# 02-Power.net
KiCad netlist of a schematic drawn in Altium Designer
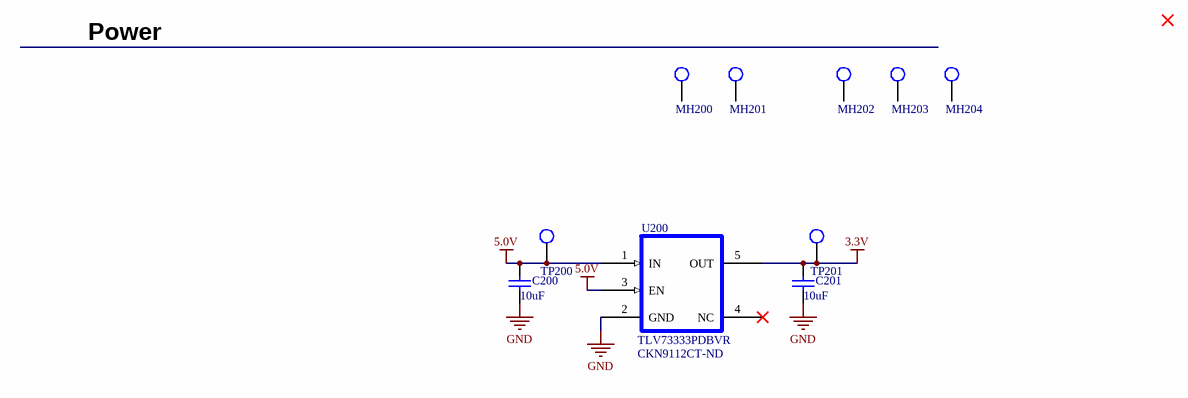
[diagram p0: 02-Power.SchDoc]

(export (version "E")
  (design (tool "Eeschema 10.0.6"))
  (components
    (comp (ref "C200")
      (value "10uF")
      (footprint "CAP_0805")
      (description "CAP CER 10UF 16V X5R 0805")
      (fields
        (field (name "MANUFACTURER") "Samsung")
        (field (name "MANUFACTURER PART NUMBER") "CL21A106KOFNNNE")
      )
      (libsource (lib "ece315") (part "CAP_0805_U_010.00"))
    )
    (comp (ref "C201")
      (value "10uF")
      (footprint "CAP_0805")
      (description "CAP CER 10UF 16V X5R 0805")
      (fields
        (field (name "MANUFACTURER") "Samsung")
        (field (name "MANUFACTURER PART NUMBER") "CL21A106KOFNNNE")
      )
      (libsource (lib "ece315") (part "CAP_0805_U_010.00"))
    )
    (comp (ref "MH200")
      (value "MHOLE_2_55MM")
      (footprint "MHOLE_2_55MM")
      (description "Mounting Holde")
      (fields (field (name "MANUFACTURER PART NUMBER") "UW MTHOLE"))
      (libsource (lib "ece315-2018-fall") (part "MHOLE_2_55MM"))
    )
    (comp (ref "MH201")
      (value "MHOLE_2_55MM")
      (footprint "MHOLE_2_55MM")
      (description "Mounting Holde")
      (fields (field (name "MANUFACTURER PART NUMBER") "UW MTHOLE"))
      (libsource (lib "ece315-2018-fall") (part "MHOLE_2_55MM"))
    )
    (comp (ref "MH202")
      (value "MHOLE_2_55MM")
      (footprint "MHOLE_2_55MM")
      (description "Mounting Holde")
      (fields (field (name "MANUFACTURER PART NUMBER") "UW MTHOLE"))
      (libsource (lib "ece315-2018-fall") (part "MHOLE_2_55MM"))
    )
    (comp (ref "MH203")
      (value "MHOLE_2_55MM")
      (footprint "MHOLE_2_55MM")
      (description "Mounting Holde")
      (fields (field (name "MANUFACTURER PART NUMBER") "UW MTHOLE"))
      (libsource (lib "ece315-2018-fall") (part "MHOLE_2_55MM"))
    )
    (comp (ref "MH204")
      (value "MHOLE_2_55MM")
      (footprint "MHOLE_2_55MM")
      (description "Mounting Holde")
      (fields (field (name "MANUFACTURER PART NUMBER") "UW MTHOLE"))
      (libsource (lib "ece315-2018-fall") (part "MHOLE_2_55MM"))
    )
    (comp (ref "TP200")
      (value "TP_1206")
      (footprint "TP-SMC-1206")
      (description "Test Point SMD 1206")
      (fields
        (field (name "MANUFACTURER") "TE Connectivity (Tyco Electronics)")
        (field (name "MANUFACTURER PART NUMBER") "1625854-1")
      )
      (libsource (lib "ece315") (part "TP_1206"))
    )
    (comp (ref "TP201")
      (value "TP_1206")
      (footprint "TP-SMC-1206")
      (description "Test Point SMD 1206")
      (fields
        (field (name "MANUFACTURER") "TE Connectivity (Tyco Electronics)")
        (field (name "MANUFACTURER PART NUMBER") "1625854-1")
      )
      (libsource (lib "ece315") (part "TP_1206"))
    )
    (comp (ref "U200")
      (value "TLV73333PDBVR")
      (footprint "IC_TLV73333PDBVR")
      (fields
        (field (name "MANUFACTURER") "Texas Instruments")
        (field (name "SUPPLIER PART NUMBER 1") "CKN9112CT-ND")
      )
      (libsource (lib "ece315") (part "TLV73333PDBVR"))
    )
  )
  (nets
    (net (code "1") (name "3.3V") (class "Default")
      (node (ref "C201") (pin "1") (pinfunction "1_1") (pintype "passive"))
      (node (ref "TP201") (pin "1") (pintype "passive"))
      (node (ref "U200") (pin "5") (pinfunction "OUT_5") (pintype "passive"))
    )
    (net (code "2") (name "5.0V") (class "Default")
      (node (ref "C200") (pin "1") (pinfunction "1_1") (pintype "passive"))
      (node (ref "TP200") (pin "1") (pintype "passive"))
      (node (ref "U200") (pin "1") (pinfunction "IN_1") (pintype "input"))
      (node (ref "U200") (pin "3") (pinfunction "EN_3") (pintype "input"))
    )
    (net (code "3") (name "GND") (class "Default")
      (node (ref "C200") (pin "2") (pinfunction "2_2") (pintype "passive"))
      (node (ref "C201") (pin "2") (pinfunction "2_2") (pintype "passive"))
      (node (ref "U200") (pin "2") (pinfunction "GND_2") (pintype "power_in"))
    )
    (net (code "4") (name "unconnected-(MH200-Pad1)") (class "Default")
      (node (ref "MH200") (pin "1") (pintype "passive"))
    )
    (net (code "5") (name "unconnected-(MH201-Pad1)") (class "Default")
      (node (ref "MH201") (pin "1") (pintype "passive"))
    )
    (net (code "6") (name "unconnected-(MH202-Pad1)") (class "Default")
      (node (ref "MH202") (pin "1") (pintype "passive"))
    )
    (net (code "7") (name "unconnected-(MH203-Pad1)") (class "Default")
      (node (ref "MH203") (pin "1") (pintype "passive"))
    )
    (net (code "8") (name "unconnected-(MH204-Pad1)") (class "Default")
      (node (ref "MH204") (pin "1") (pintype "passive"))
    )
    (net (code "9") (name "unconnected-(U200-NC-Pad4)") (class "Default")
      (node (ref "U200") (pin "4") (pinfunction "NC_4") (pintype "passive+no_connect"))
    )
  )
)
